# 27_PP0_GPP_SPI.net
KiCad netlist of a schematic drawn in Altium Designer
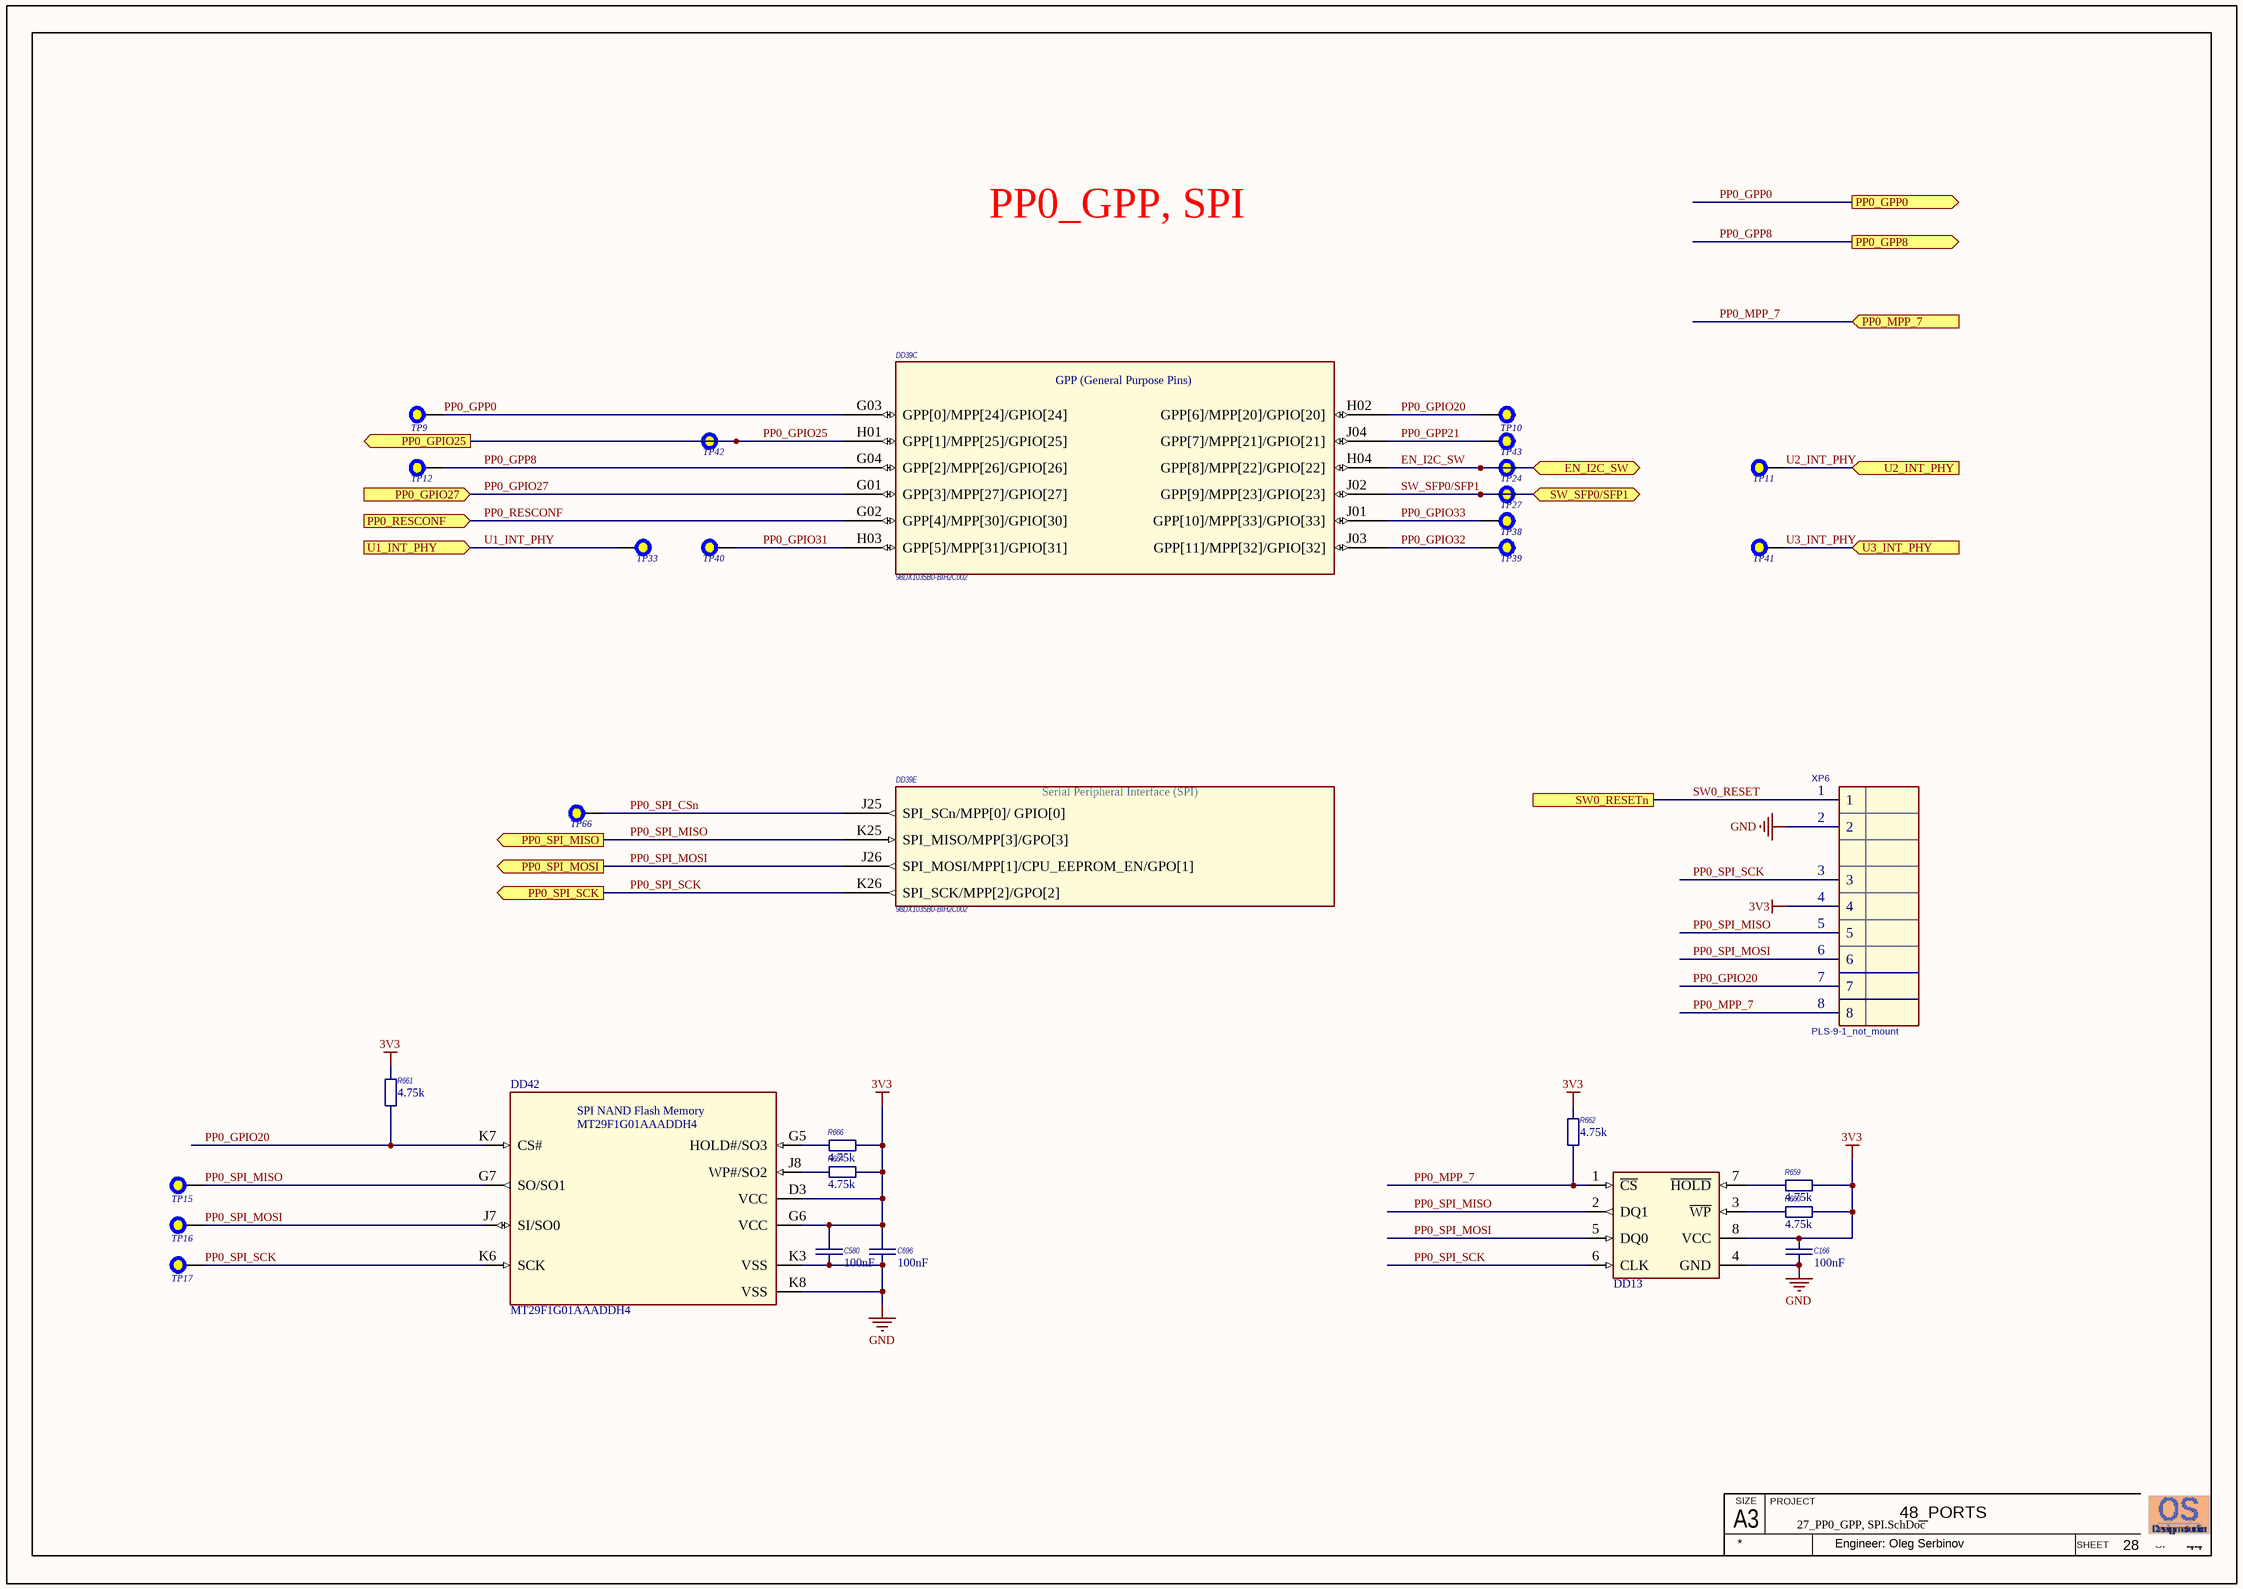
[diagram p0: 27_PP0_GPP, SPI.SchDoc]

(export (version "E")
  (design (tool "Eeschema 10.0.6"))
  (components
    (comp (ref "C166")
      (value "GRM155R71E104KE14D")
      (footprint "C0402_IPC High Density")
      (description "C0402, 100nF, 25V, X7R")
      (fields
        (field (name "MANUFACTURER") "Murata")
        (field (name "CAPACITANCE") "100nF")
        (field (name "CUSTOMER PART NUMBER") "Конденсатор, 100n, 0402, 25V, X7R, 10%")
      )
      (libsource (lib "CAPACITORS") (part "GRM155R71E104KE14D"))
    )
    (comp (ref "C580")
      (value "GRM155R71E104KE14D")
      (footprint "C0402_IPC High Density")
      (description "C0402, 100nF, 25V, X7R")
      (fields
        (field (name "MANUFACTURER") "Murata")
        (field (name "CAPACITANCE") "100nF")
        (field (name "CUSTOMER PART NUMBER") "Конденсатор, 100n, 0402, 25V, X7R, 10%")
      )
      (libsource (lib "CAPACITORS") (part "GRM155R71E104KE14D"))
    )
    (comp (ref "C696")
      (value "GRM155R71E104KE14D")
      (footprint "C0402_IPC High Density")
      (description "C0402, 100nF, 25V, X7R")
      (fields
        (field (name "MANUFACTURER") "Murata")
        (field (name "CAPACITANCE") "100nF")
        (field (name "CUSTOMER PART NUMBER") "Конденсатор, 100n, 0402, 25V, X7R, 10%")
      )
      (libsource (lib "CAPACITORS") (part "GRM155R71E104KE14D"))
    )
    (comp (ref "DD13")
      (value "M25P16-VMN6P")
      (footprint "SO-8_L")
      (description "NOR Flash Serial-SPI 3.3V 16Mbit 2M x 8bit 1 8-Pin SO N")
      (fields
        (field (name "CUSTOMER PART NUMBER") "Микросхема, M25P16-VMN6P, IC FLASH 16MBIT 75MHZ, 8-SO")
        (field (name "MANUFACTURER") "Micron Technology Inc.")
      )
      (libsource (lib "DIGITAL and ANALIG ICs") (part "M25P16-VMN6P"))
    )
    (comp (ref "DD39")
      (value "98DX1035B0-BIH2C002")
      (footprint "HSBGA617_27X27_1MM")
      (description "IC 24-PORT FE  4-PORT 2.5GE L2 ENTRY-LEVEL, CPU")
      (fields
        (field (name "CUSTOMER PART NUMBER") "Микросхема, 98DX1035B0-BIH2C002, IC 24-PORT FE 4-PORT 2.5GE L2 ENTRY-LEVEL, HSBGA617SBGA617")
        (field (name "MANUFACTURER") "Marvell Technology Group")
      )
      (libsource (lib "DIGITAL and ANALIG ICs") (part "98DX1035A1-BIH2C002"))
    )
    (comp (ref "DD42")
      (value "MT29F1G01AAADDH4")
      (footprint "VFBGA 63-Ball")
      (description "IC 1Gb x1: SPI NAND Flash Memory")
      (fields
        (field (name "MANUFACTURER") "Micron Technology Inc")
        (field (name "CUSTOMER PART NUMBER") "Микросхема, MT29F1G01AAADDH4, IC FLASH 1GBIT, 63-VFBGA")
      )
      (libsource (lib "DIGITAL and ANALIG ICs") (part "MT29F1G01AAADDH4"))
    )
    (comp (ref "R659")
      (value "ERJ-2RKF4751X")
      (footprint "R0402_IPC High Density")
      (description "R0402, 4.75k 1%")
      (fields
        (field (name "TOLERANCE") "±1%")
        (field (name "MANUFACTURER") "Panasonic")
        (field (name "RESISTANCE (OHMS)") "4.75k")
      )
      (libsource (lib "RESISTOR") (part "ERJ-2RKF4751X"))
    )
    (comp (ref "R660")
      (value "ERJ-2RKF4751X")
      (footprint "R0402_IPC High Density")
      (description "R0402, 4.75k 1%")
      (fields
        (field (name "TOLERANCE") "±1%")
        (field (name "MANUFACTURER") "Panasonic")
        (field (name "RESISTANCE (OHMS)") "4.75k")
      )
      (libsource (lib "RESISTOR") (part "ERJ-2RKF4751X"))
    )
    (comp (ref "R661")
      (value "ERJ-2RKF4751X")
      (footprint "R0402_IPC High Density")
      (description "R0402, 4.75k 1%")
      (fields
        (field (name "TOLERANCE") "±1%")
        (field (name "MANUFACTURER") "Panasonic")
        (field (name "RESISTANCE (OHMS)") "4.75k")
      )
      (libsource (lib "RESISTOR") (part "ERJ-2RKF4751X"))
    )
    (comp (ref "R662")
      (value "ERJ-2RKF4751X")
      (footprint "R0402_IPC High Density")
      (description "R0402, 4.75k 1%")
      (fields
        (field (name "TOLERANCE") "±1%")
        (field (name "MANUFACTURER") "Panasonic")
        (field (name "RESISTANCE (OHMS)") "4.75k")
      )
      (libsource (lib "RESISTOR") (part "ERJ-2RKF4751X"))
    )
    (comp (ref "R664")
      (value "ERJ-2RKF4751X")
      (footprint "R0402_IPC High Density")
      (description "R0402, 4.75k 1%")
      (fields
        (field (name "TOLERANCE") "±1%")
        (field (name "MANUFACTURER") "Panasonic")
        (field (name "RESISTANCE (OHMS)") "4.75k")
      )
      (libsource (lib "RESISTOR") (part "ERJ-2RKF4751X"))
    )
    (comp (ref "R666")
      (value "ERJ-2RKF4751X")
      (footprint "R0402_IPC High Density")
      (description "R0402, 4.75k 1%")
      (fields
        (field (name "TOLERANCE") "±1%")
        (field (name "MANUFACTURER") "Panasonic")
        (field (name "RESISTANCE (OHMS)") "4.75k")
      )
      (libsource (lib "RESISTOR") (part "ERJ-2RKF4751X"))
    )
    (comp (ref "TP9")
      (value "Test Point 0.5mm pad")
      (footprint "Test Point 0.5mm")
      (libsource (lib "CONNECTORS") (part "Test Point 0.5mm pad"))
    )
    (comp (ref "TP10")
      (value "Test Point 0.5mm pad")
      (footprint "Test Point 0.5mm")
      (libsource (lib "CONNECTORS") (part "Test Point 0.5mm pad"))
    )
    (comp (ref "TP11")
      (value "Test Point 0.5mm pad")
      (footprint "Test Point 0.5mm")
      (libsource (lib "CONNECTORS") (part "Test Point 0.5mm pad"))
    )
    (comp (ref "TP12")
      (value "Test Point 0.5mm pad")
      (footprint "Test Point 0.5mm")
      (libsource (lib "CONNECTORS") (part "Test Point 0.5mm pad"))
    )
    (comp (ref "TP15")
      (value "Test Point 0.5mm pad")
      (footprint "Test Point 0.5mm")
      (libsource (lib "CONNECTORS") (part "Test Point 0.5mm pad"))
    )
    (comp (ref "TP16")
      (value "Test Point 0.5mm pad")
      (footprint "Test Point 0.5mm")
      (libsource (lib "CONNECTORS") (part "Test Point 0.5mm pad"))
    )
    (comp (ref "TP17")
      (value "Test Point 0.5mm pad")
      (footprint "Test Point 0.5mm")
      (libsource (lib "CONNECTORS") (part "Test Point 0.5mm pad"))
    )
    (comp (ref "TP24")
      (value "Test Point 0.5mm pad")
      (footprint "Test Point 0.5mm")
      (libsource (lib "CONNECTORS") (part "Test Point 0.5mm pad"))
    )
    (comp (ref "TP27")
      (value "Test Point 0.5mm pad")
      (footprint "Test Point 0.5mm")
      (libsource (lib "CONNECTORS") (part "Test Point 0.5mm pad"))
    )
    (comp (ref "TP33")
      (value "Test Point 0.5mm pad")
      (footprint "Test Point 0.5mm")
      (libsource (lib "CONNECTORS") (part "Test Point 0.5mm pad"))
    )
    (comp (ref "TP38")
      (value "Test Point 0.5mm pad")
      (footprint "Test Point 0.5mm")
      (libsource (lib "CONNECTORS") (part "Test Point 0.5mm pad"))
    )
    (comp (ref "TP39")
      (value "Test Point 0.5mm pad")
      (footprint "Test Point 0.5mm")
      (libsource (lib "CONNECTORS") (part "Test Point 0.5mm pad"))
    )
    (comp (ref "TP40")
      (value "Test Point 0.5mm pad")
      (footprint "Test Point 0.5mm")
      (libsource (lib "CONNECTORS") (part "Test Point 0.5mm pad"))
    )
    (comp (ref "TP41")
      (value "Test Point 0.5mm pad")
      (footprint "Test Point 0.5mm")
      (libsource (lib "CONNECTORS") (part "Test Point 0.5mm pad"))
    )
    (comp (ref "TP42")
      (value "Test Point 0.5mm pad")
      (footprint "Test Point 0.5mm")
      (libsource (lib "CONNECTORS") (part "Test Point 0.5mm pad"))
    )
    (comp (ref "TP43")
      (value "Test Point 0.5mm pad")
      (footprint "Test Point 0.5mm")
      (libsource (lib "CONNECTORS") (part "Test Point 0.5mm pad"))
    )
    (comp (ref "TP66")
      (value "Test Point 0.5mm pad")
      (footprint "Test Point 0.5mm")
      (libsource (lib "CONNECTORS") (part "Test Point 0.5mm pad"))
    )
    (comp (ref "XP6")
      (value "PLS-9-1_not_mount")
      (footprint "PLS-9-1")
      (description "Connector PLS-9 (pin 3 is removed)")
      (fields
        (field (name "CUSTOMER PART NUMBER") "Разъем, PLS-9-1, 9 Positions Header pin 3 is removed,  2.54mm Through Hole Tin-Lead")
      )
      (libsource (lib "CONNECTORS") (part "PLS-9-1_not_mount"))
    )
  )
  (nets
    (net (code "1") (name "/EN_I2C_SW") (class "Default")
      (node (ref "DD39") (pin "H04") (pinfunction "GPP[8]/MPP[22]/GPIO[22]_H04") (pintype "bidirectional"))
      (node (ref "TP24") (pin "1") (pinfunction "1_1") (pintype "passive"))
    )
    (net (code "2") (name "/PP0_GPIO20") (class "Default")
      (node (ref "DD39") (pin "H02") (pinfunction "GPP[6]/MPP[20]/GPIO[20]_H02") (pintype "bidirectional"))
      (node (ref "DD42") (pin "K7") (pinfunction "CS#_K7") (pintype "input"))
      (node (ref "R661") (pin "2") (pintype "passive"))
      (node (ref "TP10") (pin "1") (pinfunction "1_1") (pintype "passive"))
      (node (ref "XP6") (pin "7") (pinfunction "7_7") (pintype "passive"))
    )
    (net (code "3") (name "/PP0_GPIO25") (class "Default")
      (node (ref "DD39") (pin "H01") (pinfunction "GPP[1]/MPP[25]/GPIO[25]_H01") (pintype "bidirectional"))
      (node (ref "TP42") (pin "1") (pinfunction "1_1") (pintype "passive"))
    )
    (net (code "4") (name "/PP0_GPIO27") (class "Default")
      (node (ref "DD39") (pin "G01") (pinfunction "GPP[3]/MPP[27]/GPIO[27]_G01") (pintype "bidirectional"))
    )
    (net (code "5") (name "/PP0_GPIO31") (class "Default")
      (node (ref "DD39") (pin "H03") (pinfunction "GPP[5]/MPP[31]/GPIO[31]_H03") (pintype "bidirectional"))
      (node (ref "TP40") (pin "1") (pinfunction "1_1") (pintype "passive"))
    )
    (net (code "6") (name "/PP0_GPIO32") (class "Default")
      (node (ref "DD39") (pin "J03") (pinfunction "GPP[11]/MPP[32]/GPIO[32]_J03") (pintype "bidirectional"))
      (node (ref "TP39") (pin "1") (pinfunction "1_1") (pintype "passive"))
    )
    (net (code "7") (name "/PP0_GPIO33") (class "Default")
      (node (ref "DD39") (pin "J01") (pinfunction "GPP[10]/MPP[33]/GPIO[33]_J01") (pintype "bidirectional"))
      (node (ref "TP38") (pin "1") (pinfunction "1_1") (pintype "passive"))
    )
    (net (code "8") (name "/PP0_GPP0") (class "Default")
      (node (ref "DD39") (pin "G03") (pinfunction "GPP[0]/MPP[24]/GPIO[24]_G03") (pintype "bidirectional"))
      (node (ref "TP9") (pin "1") (pinfunction "1_1") (pintype "passive"))
    )
    (net (code "9") (name "/PP0_GPP8") (class "Default")
      (node (ref "DD39") (pin "G04") (pinfunction "GPP[2]/MPP[26]/GPIO[26]_G04") (pintype "bidirectional"))
      (node (ref "TP12") (pin "1") (pinfunction "1_1") (pintype "passive"))
    )
    (net (code "10") (name "/PP0_GPP21") (class "Default")
      (node (ref "DD39") (pin "J04") (pinfunction "GPP[7]/MPP[21]/GPIO[21]_J04") (pintype "bidirectional"))
      (node (ref "TP43") (pin "1") (pinfunction "1_1") (pintype "passive"))
    )
    (net (code "11") (name "/PP0_MPP_7") (class "Default")
      (node (ref "DD13") (pin "1") (pinfunction "~{CS}_1") (pintype "input"))
      (node (ref "R662") (pin "2") (pintype "passive"))
      (node (ref "XP6") (pin "8") (pinfunction "8_8") (pintype "passive"))
    )
    (net (code "12") (name "/PP0_RESCONF") (class "Default")
      (node (ref "DD39") (pin "G02") (pinfunction "GPP[4]/MPP[30]/GPIO[30]_G02") (pintype "bidirectional"))
    )
    (net (code "13") (name "/PP0_SPI_CSn") (class "Default")
      (node (ref "DD39") (pin "J25") (pinfunction "SPI_SCn/MPP[0]/_GPIO[0]_J25") (pintype "output"))
      (node (ref "TP66") (pin "1") (pinfunction "1_1") (pintype "passive"))
    )
    (net (code "14") (name "/PP0_SPI_MISO") (class "Default")
      (node (ref "DD13") (pin "2") (pinfunction "DQ1_2") (pintype "output"))
      (node (ref "DD39") (pin "K25") (pinfunction "SPI_MISO/MPP[3]/GPO[3]_K25") (pintype "input"))
      (node (ref "DD42") (pin "G7") (pinfunction "SO/SO1_G7") (pintype "output"))
      (node (ref "TP15") (pin "1") (pinfunction "1_1") (pintype "passive"))
      (node (ref "XP6") (pin "5") (pinfunction "5_5") (pintype "passive"))
    )
    (net (code "15") (name "/PP0_SPI_MOSI") (class "Default")
      (node (ref "DD13") (pin "5") (pinfunction "DQ0_5") (pintype "input"))
      (node (ref "DD39") (pin "J26") (pinfunction "SPI_MOSI/MPP[1]/CPU_EEPROM_EN/GPO[1]_J26") (pintype "output"))
      (node (ref "DD42") (pin "J7") (pinfunction "SI/SO0_J7") (pintype "bidirectional"))
      (node (ref "TP16") (pin "1") (pinfunction "1_1") (pintype "passive"))
      (node (ref "XP6") (pin "6") (pinfunction "6_6") (pintype "passive"))
    )
    (net (code "16") (name "/PP0_SPI_SCK") (class "Default")
      (node (ref "DD13") (pin "6") (pinfunction "CLK_6") (pintype "input"))
      (node (ref "DD39") (pin "K26") (pinfunction "SPI_SCK/MPP[2]/GPO[2]_K26") (pintype "output"))
      (node (ref "DD42") (pin "K6") (pinfunction "SCK_K6") (pintype "input"))
      (node (ref "TP17") (pin "1") (pinfunction "1_1") (pintype "passive"))
      (node (ref "XP6") (pin "3") (pinfunction "3_3") (pintype "passive"))
    )
    (net (code "17") (name "/SW0_RESET") (class "Default")
      (node (ref "XP6") (pin "1") (pinfunction "1_1") (pintype "passive"))
    )
    (net (code "18") (name "/SW_SFP0{slash}SFP1") (class "Default")
      (node (ref "DD39") (pin "J02") (pinfunction "GPP[9]/MPP[23]/GPIO[23]_J02") (pintype "bidirectional"))
      (node (ref "TP27") (pin "1") (pinfunction "1_1") (pintype "passive"))
    )
    (net (code "19") (name "/U1_INT_PHY") (class "Default")
      (node (ref "TP33") (pin "1") (pinfunction "1_1") (pintype "passive"))
    )
    (net (code "20") (name "/U2_INT_PHY") (class "Default")
      (node (ref "TP11") (pin "1") (pinfunction "1_1") (pintype "passive"))
    )
    (net (code "21") (name "/U3_INT_PHY") (class "Default")
      (node (ref "TP41") (pin "1") (pinfunction "1_1") (pintype "passive"))
    )
    (net (code "22") (name "3V3") (class "Default")
      (node (ref "C166") (pin "1") (pintype "passive"))
      (node (ref "C580") (pin "1") (pintype "passive"))
      (node (ref "C696") (pin "1") (pintype "passive"))
      (node (ref "DD13") (pin "8") (pinfunction "VCC_8") (pintype "power_in"))
      (node (ref "DD42") (pin "D3") (pinfunction "VСС_D3") (pintype "power_in"))
      (node (ref "DD42") (pin "G6") (pinfunction "VCC_G6") (pintype "power_in"))
      (node (ref "R659") (pin "2") (pintype "passive"))
      (node (ref "R660") (pin "2") (pintype "passive"))
      (node (ref "R661") (pin "1") (pintype "passive"))
      (node (ref "R662") (pin "1") (pintype "passive"))
      (node (ref "R664") (pin "1") (pintype "passive"))
      (node (ref "R666") (pin "1") (pintype "passive"))
      (node (ref "XP6") (pin "4") (pinfunction "4_4") (pintype "passive"))
    )
    (net (code "23") (name "GND") (class "Default")
      (node (ref "C166") (pin "2") (pintype "passive"))
      (node (ref "C580") (pin "2") (pintype "passive"))
      (node (ref "C696") (pin "2") (pintype "passive"))
      (node (ref "DD13") (pin "4") (pinfunction "GND_4") (pintype "power_in"))
      (node (ref "DD42") (pin "K3") (pinfunction "VSS_K3") (pintype "power_in"))
      (node (ref "DD42") (pin "K8") (pinfunction "VSS_K8") (pintype "power_in"))
      (node (ref "XP6") (pin "2") (pinfunction "2_2") (pintype "passive"))
    )
    (net (code "24") (name "Net-(DD13-~{HOLD})") (class "Default")
      (node (ref "DD13") (pin "7") (pinfunction "~{HOLD}_7") (pintype "input"))
      (node (ref "R659") (pin "1") (pintype "passive"))
    )
    (net (code "25") (name "Net-(DD13-~{WP})") (class "Default")
      (node (ref "DD13") (pin "3") (pinfunction "~{WP}_3") (pintype "input"))
      (node (ref "R660") (pin "1") (pintype "passive"))
    )
    (net (code "26") (name "Net-(DD42-HOLD#{slash}SO3)") (class "Default")
      (node (ref "DD42") (pin "G5") (pinfunction "HOLD#/SO3_G5") (pintype "input"))
      (node (ref "R666") (pin "2") (pintype "passive"))
    )
    (net (code "27") (name "Net-(DD42-WP#{slash}SO2)") (class "Default")
      (node (ref "DD42") (pin "J8") (pinfunction "WP#/SO2_J8") (pintype "input"))
      (node (ref "R664") (pin "2") (pintype "passive"))
    )
  )
)
